# arduino_tx.net
KiCad netlist of a schematic drawn in EAGLE
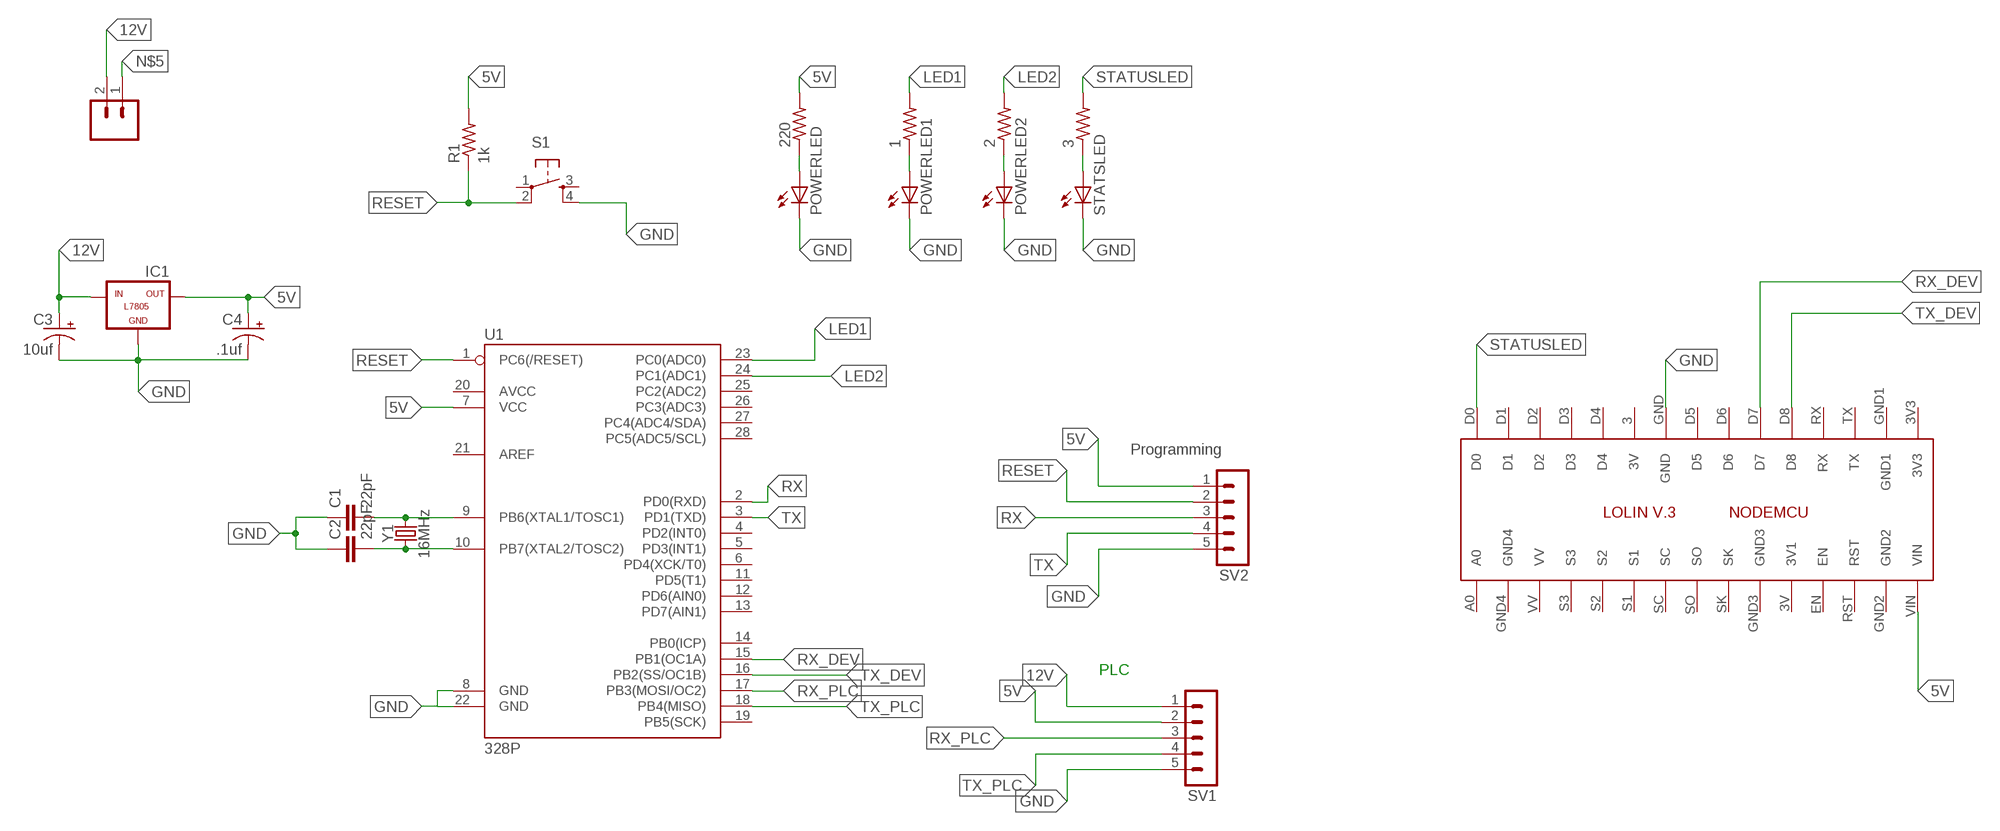
[diagram p0: schematic, sheet 1]

(export (version "E")
  (design (tool "Eeschema 10.0.6"))
  (components
    (comp (ref "1")
      (value "R-US_0204/5")
      (footprint "eagle-import:0204_5")
      (libsource (lib "eagle-import") (part "R-US_0204/5"))
    )
    (comp (ref "2")
      (value "R-US_0204/5")
      (footprint "eagle-import:0204_5")
      (libsource (lib "eagle-import") (part "R-US_0204/5"))
    )
    (comp (ref "3")
      (value "R-US_0204/5")
      (footprint "eagle-import:0204_5")
      (libsource (lib "eagle-import") (part "R-US_0204/5"))
    )
    (comp (ref "220")
      (value "R-US_0204/5")
      (footprint "eagle-import:0204_5")
      (libsource (lib "eagle-import") (part "R-US_0204/5"))
    )
    (comp (ref "C1")
      (value "22pF")
      (footprint "eagle-import:CAP-PTH-2.54")
      (libsource (lib "eagle-import") (part "22PF-PTH-2.54MM-200V-5%"))
    )
    (comp (ref "C2")
      (value "22pF")
      (footprint "eagle-import:CAP-PTH-2.54")
      (libsource (lib "eagle-import") (part "22PF-PTH-2.54MM-200V-5%"))
    )
    (comp (ref "C3")
      (value "10uf")
      (footprint "eagle-import:E5-5")
      (libsource (lib "eagle-import") (part "CPOL-USE5-5"))
    )
    (comp (ref "C4")
      (value ".1uf")
      (footprint "eagle-import:E5-5")
      (libsource (lib "eagle-import") (part "CPOL-USE5-5"))
    )
    (comp (ref "IC1")
      (value "L7805")
      (footprint "eagle-import:78XXL")
      (libsource (lib "eagle-import") (part "L7805"))
    )
    (comp (ref "IC2")
      (value "NODEMCU_LOLINV3")
      (footprint "eagle-import:NODEMCU_LOLINV3")
      (libsource (lib "eagle-import") (part "NODEMCU_LOLINV3"))
    )
    (comp (ref "J1")
      (value "CONN_025MM")
      (footprint "eagle-import:SCREWTERMINAL-5MM-2")
      (libsource (lib "eagle-import") (part "CONN_025MM"))
    )
    (comp (ref "POWERLED")
      (value "LED5MM")
      (footprint "eagle-import:LED5MM")
      (libsource (lib "eagle-import") (part "LED5MM"))
    )
    (comp (ref "POWERLED1")
      (value "LED5MM")
      (footprint "eagle-import:LED5MM")
      (libsource (lib "eagle-import") (part "LED5MM"))
    )
    (comp (ref "POWERLED2")
      (value "LED5MM")
      (footprint "eagle-import:LED5MM")
      (libsource (lib "eagle-import") (part "LED5MM"))
    )
    (comp (ref "R1")
      (value "1k")
      (footprint "eagle-import:0204_5")
      (libsource (lib "eagle-import") (part "R-US_0204/5"))
    )
    (comp (ref "S1")
      (value "TAC_SWITCHPTH")
      (footprint "eagle-import:TACTILE-PTH")
      (libsource (lib "eagle-import") (part "TAC_SWITCHPTH"))
    )
    (comp (ref "STATSLED")
      (value "LED5MM")
      (footprint "eagle-import:LED5MM")
      (libsource (lib "eagle-import") (part "LED5MM"))
    )
    (comp (ref "SV1")
      (value "MA05-1")
      (footprint "eagle-import:MA05-1")
      (libsource (lib "eagle-import") (part "MA05-1"))
    )
    (comp (ref "SV2")
      (value "MA05-1")
      (footprint "eagle-import:MA05-1")
      (libsource (lib "eagle-import") (part "MA05-1"))
    )
    (comp (ref "U1")
      (value "328P")
      (footprint "eagle-import:DIP28")
      (libsource (lib "eagle-import") (part "ATMEGA328P_PDIP"))
    )
    (comp (ref "Y1")
      (value "16MHz")
      (footprint "eagle-import:HC49US")
      (libsource (lib "eagle-import") (part "CRYSTAL-16MHZPTH-HC49US"))
    )
  )
  (nets
    (net (code "1") (name "5V") (class "Default")
      (node (ref "220") (pin "2") (pinfunction "2_2") (pintype "passive"))
      (node (ref "C4") (pin "+") (pinfunction "+_+") (pintype "passive"))
      (node (ref "IC1") (pin "OUT") (pinfunction "OUT_OUT") (pintype "passive"))
      (node (ref "IC2") (pin "VIN") (pinfunction "VIN_VIN") (pintype "bidirectional"))
      (node (ref "R1") (pin "2") (pinfunction "2_2") (pintype "passive"))
      (node (ref "SV1") (pin "2") (pinfunction "2_2") (pintype "passive"))
      (node (ref "SV2") (pin "1") (pinfunction "1_1") (pintype "passive"))
      (node (ref "U1") (pin "7") (pinfunction "VCC_7") (pintype "bidirectional"))
    )
    (net (code "2") (name "12V") (class "Default")
      (node (ref "C3") (pin "+") (pinfunction "+_+") (pintype "passive"))
      (node (ref "IC1") (pin "IN") (pinfunction "IN_IN") (pintype "input"))
      (node (ref "J1") (pin "2") (pinfunction "2_2") (pintype "passive"))
      (node (ref "SV1") (pin "1") (pinfunction "1_1") (pintype "passive"))
    )
    (net (code "3") (name "GND") (class "Default")
      (node (ref "C1") (pin "1") (pinfunction "1_1") (pintype "passive"))
      (node (ref "C2") (pin "1") (pinfunction "1_1") (pintype "passive"))
      (node (ref "C3") (pin "-") (pinfunction "-_-") (pintype "passive"))
      (node (ref "C4") (pin "-") (pinfunction "-_-") (pintype "passive"))
      (node (ref "IC1") (pin "GND") (pinfunction "GND_GND") (pintype "input"))
      (node (ref "IC2") (pin "GND") (pinfunction "GND_GND") (pintype "bidirectional"))
      (node (ref "POWERLED") (pin "K") (pinfunction "C_K") (pintype "passive"))
      (node (ref "POWERLED1") (pin "K") (pinfunction "C_K") (pintype "passive"))
      (node (ref "POWERLED2") (pin "K") (pinfunction "C_K") (pintype "passive"))
      (node (ref "S1") (pin "4") (pinfunction "4_4") (pintype "passive"))
      (node (ref "STATSLED") (pin "K") (pinfunction "C_K") (pintype "passive"))
      (node (ref "SV1") (pin "5") (pinfunction "5_5") (pintype "passive"))
      (node (ref "SV2") (pin "5") (pinfunction "5_5") (pintype "passive"))
      (node (ref "U1") (pin "22") (pinfunction "GND_22") (pintype "bidirectional"))
      (node (ref "U1") (pin "8") (pinfunction "GND_8") (pintype "bidirectional"))
    )
    (net (code "4") (name "LED1") (class "Default")
      (node (ref "1") (pin "2") (pinfunction "2_2") (pintype "passive"))
      (node (ref "U1") (pin "23") (pinfunction "PC0(ADC0)_23") (pintype "bidirectional"))
    )
    (net (code "5") (name "LED2") (class "Default")
      (node (ref "2") (pin "2") (pinfunction "2_2") (pintype "passive"))
      (node (ref "U1") (pin "24") (pinfunction "PC1(ADC1)_24") (pintype "bidirectional"))
    )
    (net (code "6") (name "N$5") (class "Default")
      (node (ref "J1") (pin "1") (pinfunction "1_1") (pintype "passive"))
    )
    (net (code "7") (name "Net-(1-Pad1)") (class "Default")
      (node (ref "1") (pin "1") (pinfunction "1_1") (pintype "passive"))
      (node (ref "POWERLED1") (pin "A") (pinfunction "A_A") (pintype "passive"))
    )
    (net (code "8") (name "Net-(2-Pad1)") (class "Default")
      (node (ref "2") (pin "1") (pinfunction "1_1") (pintype "passive"))
      (node (ref "POWERLED2") (pin "A") (pinfunction "A_A") (pintype "passive"))
    )
    (net (code "9") (name "Net-(3-Pad1)") (class "Default")
      (node (ref "3") (pin "1") (pinfunction "1_1") (pintype "passive"))
      (node (ref "STATSLED") (pin "A") (pinfunction "A_A") (pintype "passive"))
    )
    (net (code "10") (name "Net-(220-Pad1)") (class "Default")
      (node (ref "220") (pin "1") (pinfunction "1_1") (pintype "passive"))
      (node (ref "POWERLED") (pin "A") (pinfunction "A_A") (pintype "passive"))
    )
    (net (code "11") (name "Net-(U1-PB6(XTAL1{slash}TOSC1))") (class "Default")
      (node (ref "C1") (pin "2") (pinfunction "2_2") (pintype "passive"))
      (node (ref "U1") (pin "9") (pinfunction "PB6(XTAL1/TOSC1)_9") (pintype "bidirectional"))
      (node (ref "Y1") (pin "2") (pinfunction "2_2") (pintype "passive"))
    )
    (net (code "12") (name "Net-(U1-PB7(XTAL2{slash}TOSC2))") (class "Default")
      (node (ref "C2") (pin "2") (pinfunction "2_2") (pintype "passive"))
      (node (ref "U1") (pin "10") (pinfunction "PB7(XTAL2/TOSC2)_10") (pintype "bidirectional"))
      (node (ref "Y1") (pin "1") (pinfunction "1_1") (pintype "passive"))
    )
    (net (code "13") (name "RESET") (class "Default")
      (node (ref "R1") (pin "1") (pinfunction "1_1") (pintype "passive"))
      (node (ref "S1") (pin "2") (pinfunction "2_2") (pintype "passive"))
      (node (ref "SV2") (pin "2") (pinfunction "2_2") (pintype "passive"))
      (node (ref "U1") (pin "1") (pinfunction "PC6(/RESET)_1") (pintype "bidirectional"))
    )
    (net (code "14") (name "RX") (class "Default")
      (node (ref "SV2") (pin "3") (pinfunction "3_3") (pintype "passive"))
      (node (ref "U1") (pin "2") (pinfunction "PD0(RXD)_2") (pintype "bidirectional"))
    )
    (net (code "15") (name "RX_DEV") (class "Default")
      (node (ref "IC2") (pin "D7") (pinfunction "D7_D7") (pintype "bidirectional"))
      (node (ref "U1") (pin "15") (pinfunction "PB1(OC1A)_15") (pintype "bidirectional"))
    )
    (net (code "16") (name "RX_PLC") (class "Default")
      (node (ref "SV1") (pin "3") (pinfunction "3_3") (pintype "passive"))
      (node (ref "U1") (pin "17") (pinfunction "PB3(MOSI/OC2)_17") (pintype "bidirectional"))
    )
    (net (code "17") (name "STATUSLED") (class "Default")
      (node (ref "3") (pin "2") (pinfunction "2_2") (pintype "passive"))
      (node (ref "IC2") (pin "D0") (pinfunction "D0_D0") (pintype "bidirectional"))
    )
    (net (code "18") (name "TX") (class "Default")
      (node (ref "SV2") (pin "4") (pinfunction "4_4") (pintype "passive"))
      (node (ref "U1") (pin "3") (pinfunction "PD1(TXD)_3") (pintype "bidirectional"))
    )
    (net (code "19") (name "TX_DEV") (class "Default")
      (node (ref "IC2") (pin "D8") (pinfunction "D8_D8") (pintype "bidirectional"))
      (node (ref "U1") (pin "16") (pinfunction "PB2(SS/OC1B)_16") (pintype "bidirectional"))
    )
    (net (code "20") (name "TX_PLC") (class "Default")
      (node (ref "SV1") (pin "4") (pinfunction "4_4") (pintype "passive"))
      (node (ref "U1") (pin "18") (pinfunction "PB4(MISO)_18") (pintype "bidirectional"))
    )
    (net (code "21") (name "unconnected-(IC2-3V-Pad3)") (class "Default")
      (node (ref "IC2") (pin "3") (pinfunction "3V_3") (pintype "bidirectional"))
    )
    (net (code "22") (name "unconnected-(IC2-3V1-Pad3V)") (class "Default")
      (node (ref "IC2") (pin "3V") (pinfunction "3V1_3V") (pintype "bidirectional"))
    )
    (net (code "23") (name "unconnected-(IC2-Pad3V3)") (class "Default")
      (node (ref "IC2") (pin "3V3") (pinfunction "3V3_3V3") (pintype "bidirectional"))
    )
    (net (code "24") (name "unconnected-(IC2-PadA0)") (class "Default")
      (node (ref "IC2") (pin "A0") (pinfunction "A0_A0") (pintype "bidirectional"))
    )
    (net (code "25") (name "unconnected-(IC2-PadD1)") (class "Default")
      (node (ref "IC2") (pin "D1") (pinfunction "D1_D1") (pintype "bidirectional"))
    )
    (net (code "26") (name "unconnected-(IC2-PadD2)") (class "Default")
      (node (ref "IC2") (pin "D2") (pinfunction "D2_D2") (pintype "bidirectional"))
    )
    (net (code "27") (name "unconnected-(IC2-PadD3)") (class "Default")
      (node (ref "IC2") (pin "D3") (pinfunction "D3_D3") (pintype "bidirectional"))
    )
    (net (code "28") (name "unconnected-(IC2-PadD4)") (class "Default")
      (node (ref "IC2") (pin "D4") (pinfunction "D4_D4") (pintype "bidirectional"))
    )
    (net (code "29") (name "unconnected-(IC2-PadD5)") (class "Default")
      (node (ref "IC2") (pin "D5") (pinfunction "D5_D5") (pintype "bidirectional"))
    )
    (net (code "30") (name "unconnected-(IC2-PadD6)") (class "Default")
      (node (ref "IC2") (pin "D6") (pinfunction "D6_D6") (pintype "bidirectional"))
    )
    (net (code "31") (name "unconnected-(IC2-PadEN)") (class "Default")
      (node (ref "IC2") (pin "EN") (pinfunction "EN_EN") (pintype "bidirectional"))
    )
    (net (code "32") (name "unconnected-(IC2-PadGND1)") (class "Default")
      (node (ref "IC2") (pin "GND1") (pinfunction "GND1_GND1") (pintype "bidirectional"))
    )
    (net (code "33") (name "unconnected-(IC2-PadGND2)") (class "Default")
      (node (ref "IC2") (pin "GND2") (pinfunction "GND2_GND2") (pintype "bidirectional"))
    )
    (net (code "34") (name "unconnected-(IC2-PadGND3)") (class "Default")
      (node (ref "IC2") (pin "GND3") (pinfunction "GND3_GND3") (pintype "bidirectional"))
    )
    (net (code "35") (name "unconnected-(IC2-PadGND4)") (class "Default")
      (node (ref "IC2") (pin "GND4") (pinfunction "GND4_GND4") (pintype "bidirectional"))
    )
    (net (code "36") (name "unconnected-(IC2-PadRST)") (class "Default")
      (node (ref "IC2") (pin "RST") (pinfunction "RST_RST") (pintype "bidirectional"))
    )
    (net (code "37") (name "unconnected-(IC2-PadRX)") (class "Default")
      (node (ref "IC2") (pin "RX") (pinfunction "RX_RX") (pintype "bidirectional"))
    )
    (net (code "38") (name "unconnected-(IC2-PadS1)") (class "Default")
      (node (ref "IC2") (pin "S1") (pinfunction "S1_S1") (pintype "bidirectional"))
    )
    (net (code "39") (name "unconnected-(IC2-PadS2)") (class "Default")
      (node (ref "IC2") (pin "S2") (pinfunction "S2_S2") (pintype "bidirectional"))
    )
    (net (code "40") (name "unconnected-(IC2-PadS3)") (class "Default")
      (node (ref "IC2") (pin "S3") (pinfunction "S3_S3") (pintype "bidirectional"))
    )
    (net (code "41") (name "unconnected-(IC2-PadSC)") (class "Default")
      (node (ref "IC2") (pin "SC") (pinfunction "SC_SC") (pintype "bidirectional"))
    )
    (net (code "42") (name "unconnected-(IC2-PadSK)") (class "Default")
      (node (ref "IC2") (pin "SK") (pinfunction "SK_SK") (pintype "bidirectional"))
    )
    (net (code "43") (name "unconnected-(IC2-PadSO)") (class "Default")
      (node (ref "IC2") (pin "SO") (pinfunction "SO_SO") (pintype "bidirectional"))
    )
    (net (code "44") (name "unconnected-(IC2-PadTX)") (class "Default")
      (node (ref "IC2") (pin "TX") (pinfunction "TX_TX") (pintype "bidirectional"))
    )
    (net (code "45") (name "unconnected-(IC2-PadVV)") (class "Default")
      (node (ref "IC2") (pin "VV") (pinfunction "VV_VV") (pintype "bidirectional"))
    )
    (net (code "46") (name "unconnected-(S1-Pad1)") (class "Default")
      (node (ref "S1") (pin "1") (pinfunction "1_1") (pintype "passive"))
    )
    (net (code "47") (name "unconnected-(S1-Pad3)") (class "Default")
      (node (ref "S1") (pin "3") (pinfunction "3_3") (pintype "passive"))
    )
    (net (code "48") (name "unconnected-(U1-AREF-Pad21)") (class "Default")
      (node (ref "U1") (pin "21") (pinfunction "AREF_21") (pintype "bidirectional"))
    )
    (net (code "49") (name "unconnected-(U1-AVCC-Pad20)") (class "Default")
      (node (ref "U1") (pin "20") (pinfunction "AVCC_20") (pintype "bidirectional"))
    )
    (net (code "50") (name "unconnected-(U1-PB0(ICP)-Pad14)") (class "Default")
      (node (ref "U1") (pin "14") (pinfunction "PB0(ICP)_14") (pintype "bidirectional"))
    )
    (net (code "51") (name "unconnected-(U1-PB5(SCK)-Pad19)") (class "Default")
      (node (ref "U1") (pin "19") (pinfunction "PB5(SCK)_19") (pintype "bidirectional"))
    )
    (net (code "52") (name "unconnected-(U1-PC2(ADC2)-Pad25)") (class "Default")
      (node (ref "U1") (pin "25") (pinfunction "PC2(ADC2)_25") (pintype "bidirectional"))
    )
    (net (code "53") (name "unconnected-(U1-PC3(ADC3)-Pad26)") (class "Default")
      (node (ref "U1") (pin "26") (pinfunction "PC3(ADC3)_26") (pintype "bidirectional"))
    )
    (net (code "54") (name "unconnected-(U1-PC4(ADC4{slash}SDA)-Pad27)") (class "Default")
      (node (ref "U1") (pin "27") (pinfunction "PC4(ADC4/SDA)_27") (pintype "bidirectional"))
    )
    (net (code "55") (name "unconnected-(U1-PC5(ADC5{slash}SCL)-Pad28)") (class "Default")
      (node (ref "U1") (pin "28") (pinfunction "PC5(ADC5/SCL)_28") (pintype "bidirectional"))
    )
    (net (code "56") (name "unconnected-(U1-PD2(INT0)-Pad4)") (class "Default")
      (node (ref "U1") (pin "4") (pinfunction "PD2(INT0)_4") (pintype "bidirectional"))
    )
    (net (code "57") (name "unconnected-(U1-PD3(INT1)-Pad5)") (class "Default")
      (node (ref "U1") (pin "5") (pinfunction "PD3(INT1)_5") (pintype "bidirectional"))
    )
    (net (code "58") (name "unconnected-(U1-PD4(XCK{slash}T0)-Pad6)") (class "Default")
      (node (ref "U1") (pin "6") (pinfunction "PD4(XCK/T0)_6") (pintype "bidirectional"))
    )
    (net (code "59") (name "unconnected-(U1-PD5(T1)-Pad11)") (class "Default")
      (node (ref "U1") (pin "11") (pinfunction "PD5(T1)_11") (pintype "bidirectional"))
    )
    (net (code "60") (name "unconnected-(U1-PD6(AIN0)-Pad12)") (class "Default")
      (node (ref "U1") (pin "12") (pinfunction "PD6(AIN0)_12") (pintype "bidirectional"))
    )
    (net (code "61") (name "unconnected-(U1-PD7(AIN1)-Pad13)") (class "Default")
      (node (ref "U1") (pin "13") (pinfunction "PD7(AIN1)_13") (pintype "bidirectional"))
    )
  )
)
